# MAX21000.net
KiCad netlist of a schematic drawn in Altium Designer
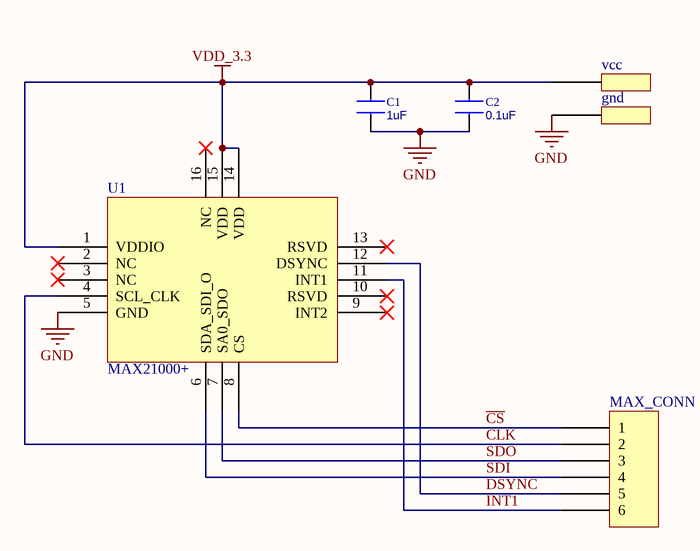
[diagram p0: MAX21000.SchDoc]

(export (version "E")
  (design (tool "Eeschema 10.0.6"))
  (components
    (comp (ref "C1")
      (value "1uF")
      (footprint "General_Lib:C_0805")
      (description "Capacitor")
      (libsource (lib "General_Lib") (part "CAP_SMD_0805"))
    )
    (comp (ref "C2")
      (value "0.1uF")
      (footprint "General_Lib:C_0805")
      (description "Capacitor")
      (libsource (lib "General_Lib") (part "CAP_SMD_0805"))
    )
    (comp (ref "gnd")
      (value "1_pin_plate_conn")
      (footprint "1_pin_plate_conn")
      (libsource (lib "AD_lib") (part "1_pin_plate_conn"))
    )
    (comp (ref "MAX_CONN")
      (value "6_pin_plate_conn")
      (footprint "6_pin_plate_conn")
      (libsource (lib "AD_lib") (part "6_pin_plate_conn"))
    )
    (comp (ref "U1")
      (value "MAX21000+")
      (footprint "PQFN50P300X300X100-16N")
      (description "3-axis digital gyroscope")
      (libsource (lib "max") (part "max21000"))
    )
    (comp (ref "vcc")
      (value "1_pin_plate_conn")
      (footprint "1_pin_plate_conn")
      (libsource (lib "AD_lib") (part "1_pin_plate_conn"))
    )
  )
  (nets
    (net (code "1") (name "/CLK") (class "Default")
      (node (ref "MAX_CONN") (pin "2") (pinfunction "2_2") (pintype "passive"))
      (node (ref "U1") (pin "4") (pinfunction "SCL_CLK_4") (pintype "passive"))
    )
    (net (code "2") (name "/DSYNC") (class "Default")
      (node (ref "MAX_CONN") (pin "5") (pinfunction "5_5") (pintype "passive"))
      (node (ref "U1") (pin "12") (pinfunction "DSYNC_12") (pintype "passive"))
    )
    (net (code "3") (name "/INT1") (class "Default")
      (node (ref "MAX_CONN") (pin "6") (pinfunction "6_6") (pintype "passive"))
      (node (ref "U1") (pin "11") (pinfunction "INT1_11") (pintype "passive"))
    )
    (net (code "4") (name "/SDI") (class "Default")
      (node (ref "MAX_CONN") (pin "4") (pinfunction "4_4") (pintype "passive"))
      (node (ref "U1") (pin "6") (pinfunction "SDA_SDI_O_6") (pintype "passive"))
    )
    (net (code "5") (name "/SDO") (class "Default")
      (node (ref "MAX_CONN") (pin "3") (pinfunction "3_3") (pintype "passive"))
      (node (ref "U1") (pin "7") (pinfunction "SA0_SDO_7") (pintype "passive"))
    )
    (net (code "6") (name "/~{CS}") (class "Default")
      (node (ref "MAX_CONN") (pin "1") (pinfunction "1_1") (pintype "passive"))
      (node (ref "U1") (pin "8") (pinfunction "CS_8") (pintype "passive"))
    )
    (net (code "7") (name "GND") (class "Default")
      (node (ref "C1") (pin "1") (pintype "passive"))
      (node (ref "C2") (pin "1") (pintype "passive"))
      (node (ref "U1") (pin "5") (pinfunction "GND_5") (pintype "passive"))
      (node (ref "gnd") (pin "1") (pinfunction "1_1") (pintype "passive"))
    )
    (net (code "8") (name "VDD_3.3") (class "Default")
      (node (ref "C1") (pin "2") (pintype "passive"))
      (node (ref "C2") (pin "2") (pintype "passive"))
      (node (ref "U1") (pin "1") (pinfunction "VDDIO_1") (pintype "passive"))
      (node (ref "U1") (pin "14") (pinfunction "VDD_14") (pintype "passive"))
      (node (ref "U1") (pin "15") (pinfunction "VDD_15") (pintype "passive"))
      (node (ref "vcc") (pin "1") (pinfunction "1_1") (pintype "passive"))
    )
    (net (code "9") (name "unconnected-(U1-INT2-Pad9)") (class "Default")
      (node (ref "U1") (pin "9") (pinfunction "INT2_9") (pintype "passive+no_connect"))
    )
    (net (code "10") (name "unconnected-(U1-NC-Pad2)") (class "Default")
      (node (ref "U1") (pin "2") (pinfunction "NC_2") (pintype "passive+no_connect"))
    )
    (net (code "11") (name "unconnected-(U1-NC-Pad3)") (class "Default")
      (node (ref "U1") (pin "3") (pinfunction "NC_3") (pintype "passive+no_connect"))
    )
    (net (code "12") (name "unconnected-(U1-NC-Pad16)") (class "Default")
      (node (ref "U1") (pin "16") (pinfunction "NC_16") (pintype "passive+no_connect"))
    )
    (net (code "13") (name "unconnected-(U1-RSVD-Pad10)") (class "Default")
      (node (ref "U1") (pin "10") (pinfunction "RSVD_10") (pintype "passive+no_connect"))
    )
    (net (code "14") (name "unconnected-(U1-RSVD-Pad13)") (class "Default")
      (node (ref "U1") (pin "13") (pinfunction "RSVD_13") (pintype "passive+no_connect"))
    )
  )
)
